# mbedTNC.net
KiCad netlist of a schematic drawn in EAGLE
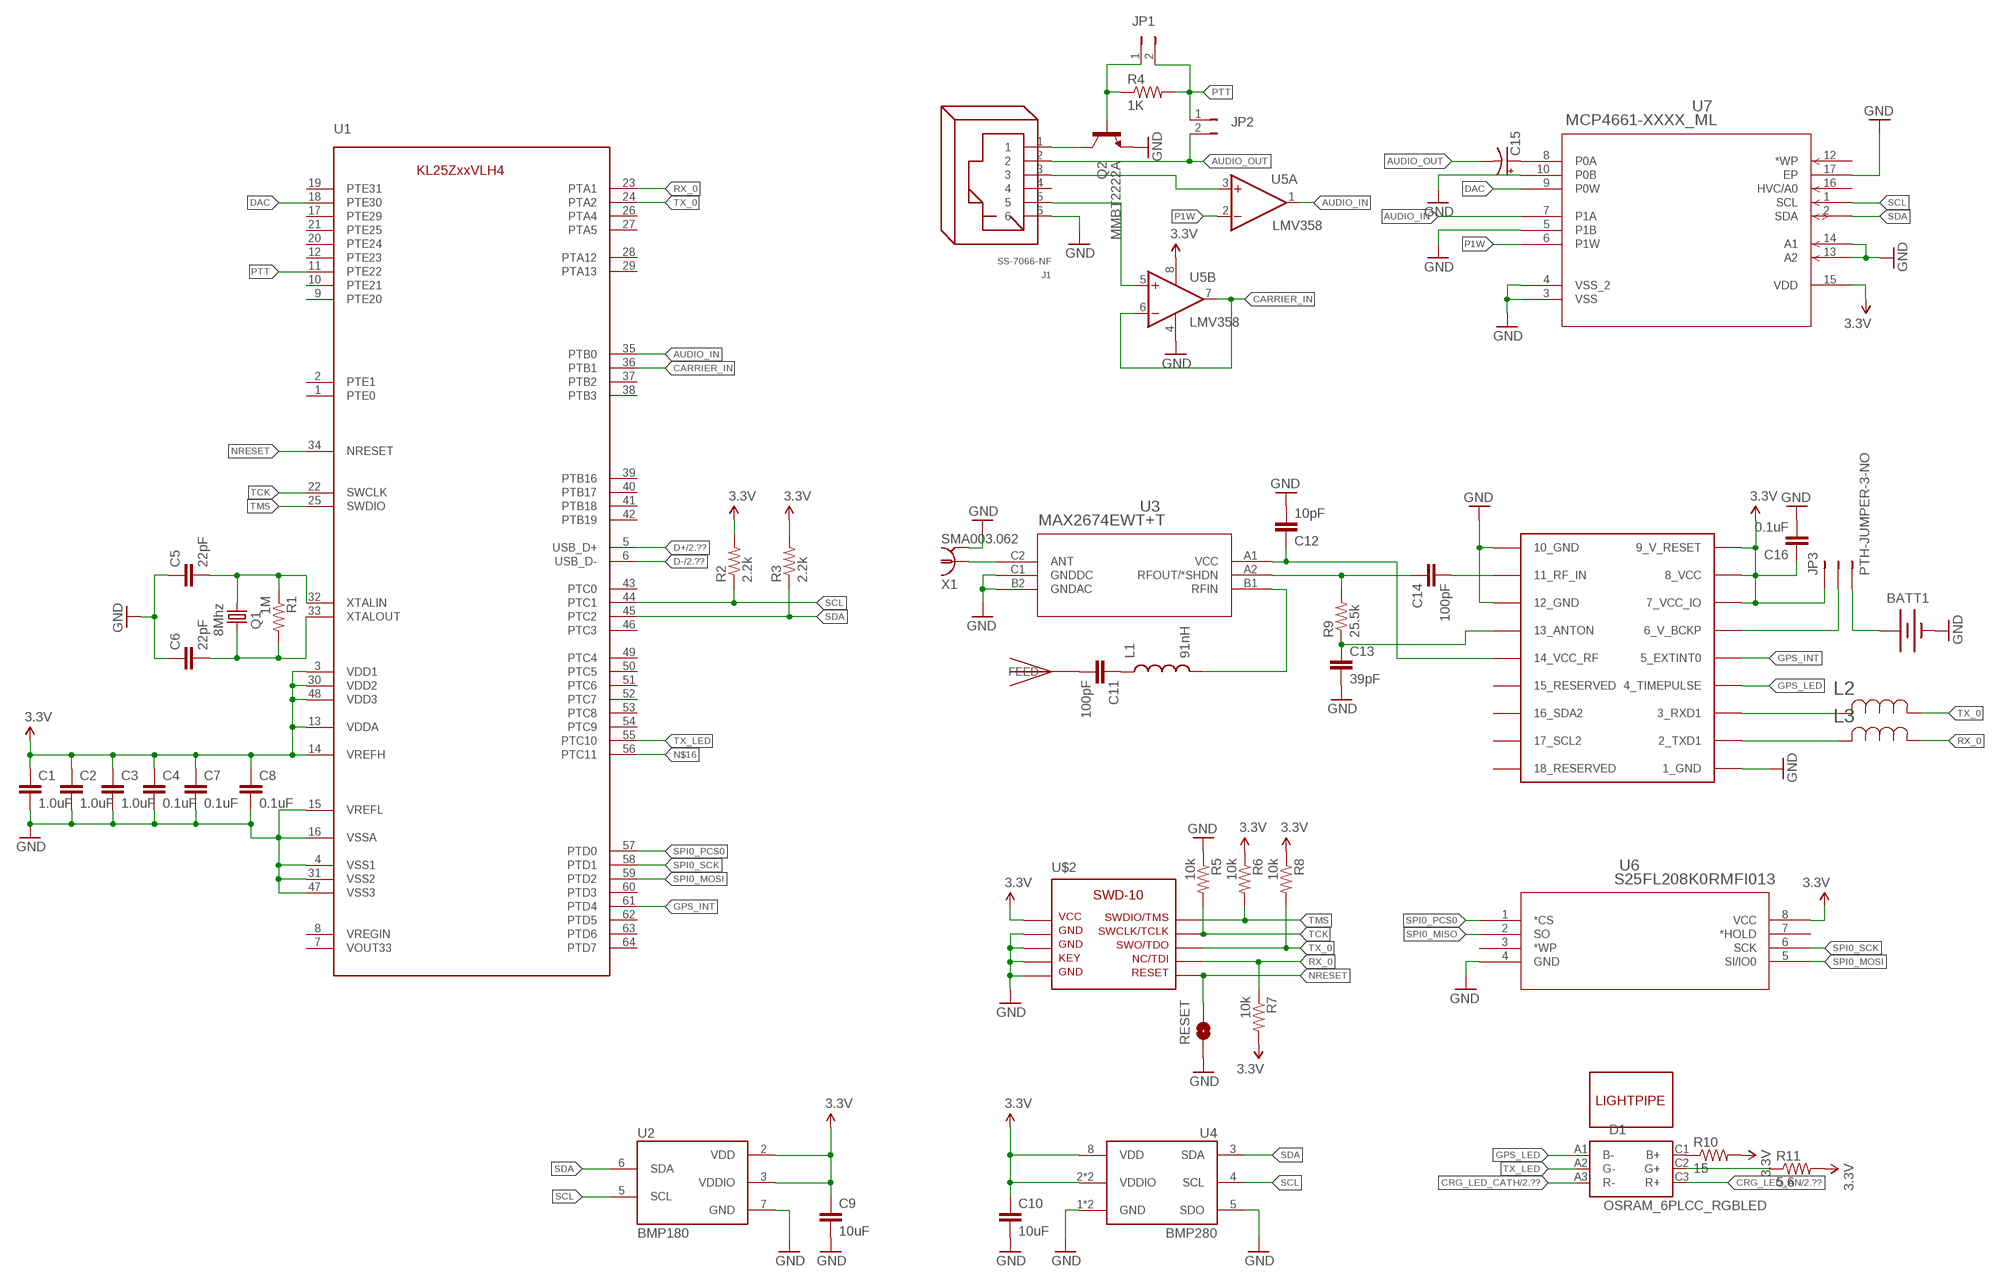
[diagram p0: schematic, sheet 1]
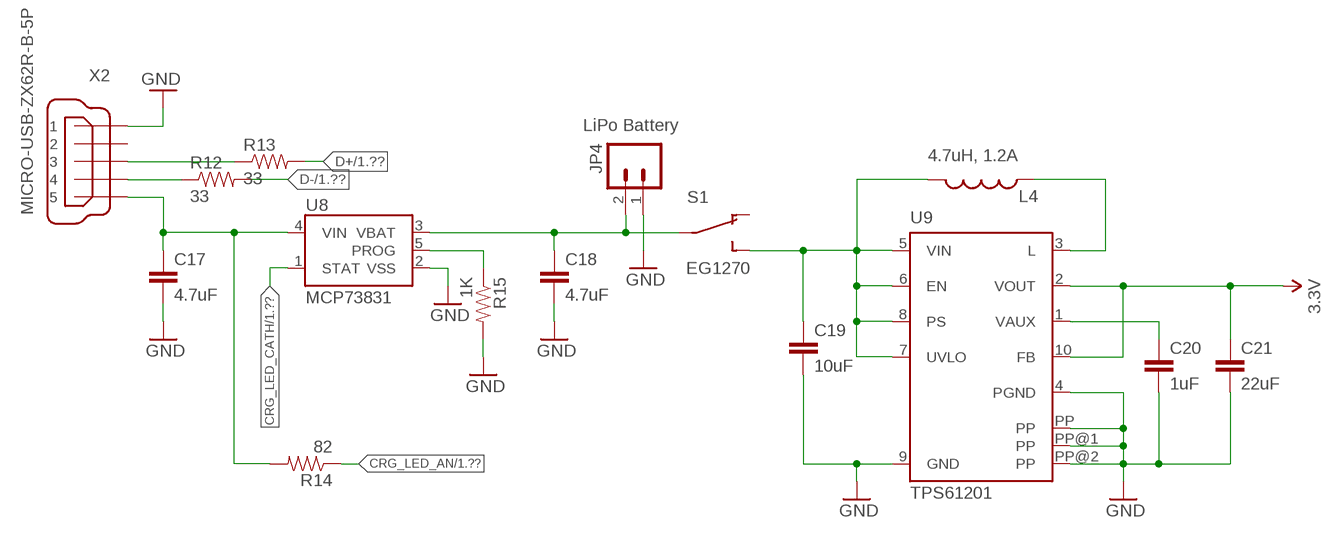
[diagram p1: schematic, sheet 2]

(export (version "E")
  (design (tool "Eeschema 10.0.6"))
  (components
    (comp (ref "C17")
      (value "4.7uF")
      (footprint "eagle-import:0805")
      (fields (field (name "MPN") "CL21B475KOFNNNE"))
      (libsource (lib "eagle-import") (part "SparkFun-Capacitors_CAP0805"))
    )
    (comp (ref "C18")
      (value "4.7uF")
      (footprint "eagle-import:0805")
      (fields (field (name "MPN") "CL21B475KOFNNNE"))
      (libsource (lib "eagle-import") (part "SparkFun-Capacitors_CAP0805"))
    )
    (comp (ref "C19")
      (value "10uF")
      (footprint "eagle-import:0805")
      (fields (field (name "MPN") "CL21A106KOQNNNE"))
      (libsource (lib "eagle-import") (part "SparkFun-Capacitors_CAP0805"))
    )
    (comp (ref "C20")
      (value "1uF")
      (footprint "eagle-import:0603-CAP")
      (fields (field (name "MPN") "EMK107B7105KA-T"))
      (libsource (lib "eagle-import") (part "SparkFun-Capacitors_CAP0603-CAP"))
    )
    (comp (ref "C21")
      (value "22uF")
      (footprint "eagle-import:1206")
      (fields (field (name "MPN") "CL31A226KOCLFNC"))
      (libsource (lib "eagle-import") (part "SparkFun-Capacitors_CAP1206"))
    )
    (comp (ref "JP4")
      (value "LiPo Battery")
      (footprint "eagle-import:JST-2-SMD")
      (fields (field (name "MPN") "S2B-PH-SM4-TB(LF)(SN)"))
      (libsource (lib "eagle-import") (part "M02-JST-2MM-SMT"))
    )
    (comp (ref "L4")
      (value "4.7uH, 1.2A")
      (footprint "eagle-import:CDRH2D09")
      (fields (field (name "MPN") "CDRH2D18/HPNP-4R7NC"))
      (libsource (lib "eagle-import") (part "INDUCTOR."))
    )
    (comp (ref "R12")
      (value "33")
      (footprint "eagle-import:0603-RES")
      (fields (field (name "MPN") "RMCF0603FT33R0"))
      (libsource (lib "eagle-import") (part "RESISTOR0603"))
    )
    (comp (ref "R13")
      (value "33")
      (footprint "eagle-import:0603-RES")
      (fields (field (name "MPN") "RMCF0603FT33R0"))
      (libsource (lib "eagle-import") (part "RESISTOR0603"))
    )
    (comp (ref "R14")
      (value "82")
      (footprint "eagle-import:0603-RES")
      (fields (field (name "MPN") "ESR03EZPJ820"))
      (libsource (lib "eagle-import") (part "RESISTOR0603"))
    )
    (comp (ref "R15")
      (value "1K")
      (footprint "eagle-import:0603-RES")
      (fields (field (name "MPN") "RMCF0603JT1K00"))
      (libsource (lib "eagle-import") (part "RESISTOR0603"))
    )
    (comp (ref "S1")
      (value "EG1270")
      (footprint "eagle-import:EG1270")
      (libsource (lib "eagle-import") (part "EG1270"))
    )
    (comp (ref "U8")
      (value "MCP73831")
      (footprint "eagle-import:SOT23-5")
      (libsource (lib "eagle-import") (part "MCP73831"))
    )
    (comp (ref "U9")
      (value "TPS61201")
      (footprint "eagle-import:S-PDSO-N10")
      (fields (field (name "MPN") "TPS61201DRCT"))
      (libsource (lib "eagle-import") (part "TPS61201"))
    )
    (comp (ref "X2")
      (value "MICRO-USB-ZX62R-B-5P")
      (footprint "eagle-import:ZX62R-B-5P")
      (fields (field (name "MPN") "ZX62R-B-5P"))
      (libsource (lib "eagle-import") (part "MICRO-USB-ZX62R-B-5P"))
    )
    (comp (ref "BATT1")
      (value "BK-890")
      (footprint "eagle-import:BATTCON_12MMPC")
      (libsource (lib "eagle-import") (part "BK-890"))
    )
    (comp (ref "C1")
      (value "1.0uF")
      (footprint "eagle-import:0603-CAP")
      (fields (field (name "MPN") "EMK107B7105KA-T"))
      (libsource (lib "eagle-import") (part "SparkFun-Capacitors_CAP0603-CAP"))
    )
    (comp (ref "C2")
      (value "1.0uF")
      (footprint "eagle-import:0603-CAP")
      (fields (field (name "MPN") "EMK107B7105KA-T"))
      (libsource (lib "eagle-import") (part "SparkFun-Capacitors_CAP0603-CAP"))
    )
    (comp (ref "C3")
      (value "1.0uF")
      (footprint "eagle-import:0603-CAP")
      (fields (field (name "MPN") "EMK107B7105KA-T"))
      (libsource (lib "eagle-import") (part "SparkFun-Capacitors_CAP0603-CAP"))
    )
    (comp (ref "C4")
      (value "0.1uF")
      (footprint "eagle-import:0603-CAP")
      (fields (field (name "MPN") "GRM188R71C104KA01D"))
      (libsource (lib "eagle-import") (part "SparkFun-Capacitors_CAP0603-CAP"))
    )
    (comp (ref "C5")
      (value "22pF")
      (footprint "eagle-import:0603-CAP")
      (fields (field (name "MPN") "C1608C0G1H220J080AA"))
      (libsource (lib "eagle-import") (part "SparkFun-Capacitors_CAP0603-CAP"))
    )
    (comp (ref "C6")
      (value "22pF")
      (footprint "eagle-import:0603-CAP")
      (fields (field (name "MPN") "C1608C0G1H220J080AA"))
      (libsource (lib "eagle-import") (part "SparkFun-Capacitors_CAP0603-CAP"))
    )
    (comp (ref "C7")
      (value "0.1uF")
      (footprint "eagle-import:0603-CAP")
      (fields (field (name "MPN") "GRM188R71C104KA01D"))
      (libsource (lib "eagle-import") (part "SparkFun-Capacitors_CAP0603-CAP"))
    )
    (comp (ref "C8")
      (value "0.1uF")
      (footprint "eagle-import:0603-CAP")
      (fields (field (name "MPN") "GRM188R71C104KA01D"))
      (libsource (lib "eagle-import") (part "SparkFun-Capacitors_CAP0603-CAP"))
    )
    (comp (ref "C9")
      (value "10uF")
      (footprint "eagle-import:0805")
      (fields (field (name "MPN") "CC0805KKX5R6BB106"))
      (libsource (lib "eagle-import") (part "SparkFun-Capacitors_CAP0805"))
    )
    (comp (ref "C10")
      (value "10uF")
      (footprint "eagle-import:0805")
      (fields (field (name "MPN") "CC0805KKX5R6BB106"))
      (libsource (lib "eagle-import") (part "SparkFun-Capacitors_CAP0805"))
    )
    (comp (ref "C11")
      (value "100pF")
      (footprint "eagle-import:0603-CAP")
      (fields (field (name "MPN") "CL10B101KB8NNNC"))
      (libsource (lib "eagle-import") (part "SparkFun-Capacitors_CAP0603-CAP"))
    )
    (comp (ref "C12")
      (value "10pF")
      (footprint "eagle-import:0603-CAP")
      (fields (field (name "MPN") "CL10C100CB8NNNC"))
      (libsource (lib "eagle-import") (part "SparkFun-Capacitors_CAP0603-CAP"))
    )
    (comp (ref "C13")
      (value "39pF")
      (footprint "eagle-import:0603-CAP")
      (fields (field (name "MPN") "CL10C390JB8NNNC"))
      (libsource (lib "eagle-import") (part "SparkFun-Capacitors_CAP0603-CAP"))
    )
    (comp (ref "C14")
      (value "100pF")
      (footprint "eagle-import:0603-CAP")
      (fields (field (name "MPN") "CL10B101KB8NNNC"))
      (libsource (lib "eagle-import") (part "SparkFun-Capacitors_CAP0603-CAP"))
    )
    (comp (ref "C15")
      (value "UWX1C100MCL2GB")
      (footprint "eagle-import:PCAP_4X5.4-ELECT")
      (libsource (lib "eagle-import") (part "UWX1C100MCL2GB"))
    )
    (comp (ref "C16")
      (value "0.1uF")
      (footprint "eagle-import:0603-CAP")
      (fields (field (name "MPN") "GRM188R71C104KA01D"))
      (libsource (lib "eagle-import") (part "CAP0603-CAP"))
    )
    (comp (ref "D1")
      (value "OSRAM_6PLCC_RGBLED")
      (footprint "eagle-import:LRTB-GFTM")
      (fields (field (name "MPN") "LRTBGFTM-ST7-1+VV9-29+Q5R"))
      (libsource (lib "eagle-import") (part "OSRAM_6PLCC_RGBLED"))
    )
    (comp (ref "J1")
      (value "SS-7066-NF")
      (footprint "eagle-import:SS-7066-NF")
      (libsource (lib "eagle-import") (part "SS-7066-NF"))
    )
    (comp (ref "JP1")
      (value "JUMPER-PTH-2-NO")
      (footprint "eagle-import:PTH-JUMPER-2-NO_NO_SILK")
      (libsource (lib "eagle-import") (part "JUMPER-PTH-2-NO"))
    )
    (comp (ref "JP2")
      (value "JUMPER-PTH-2-NO")
      (footprint "eagle-import:PTH-JUMPER-2-NO_NO_SILK")
      (libsource (lib "eagle-import") (part "JUMPER-PTH-2-NO"))
    )
    (comp (ref "JP3")
      (value "PTH-JUMPER-3-NO")
      (footprint "eagle-import:PTH-JUMPER-3-NO")
      (libsource (lib "eagle-import") (part "PTH-JUMPER-3-NO"))
    )
    (comp (ref "L1")
      (value "91nH")
      (footprint "eagle-import:0603")
      (fields (field (name "MPN") "LQW18AN91NJ00D"))
      (libsource (lib "eagle-import") (part "INDUCTOR0603"))
    )
    (comp (ref "L2")
      (value "BLM18HG102SN1D")
      (footprint "eagle-import:IND_BLM18_0603")
      (libsource (lib "eagle-import") (part "BLM18HG102SN1D"))
    )
    (comp (ref "L3")
      (value "BLM18HG102SN1D")
      (footprint "eagle-import:IND_BLM18_0603")
      (libsource (lib "eagle-import") (part "BLM18HG102SN1D"))
    )
    (comp (ref "Q1")
      (value "8Mhz")
      (footprint "eagle-import:CRYSTAL_5X3.2")
      (fields (field (name "MPN") "7A-8.000MAAJ-T "))
      (libsource (lib "eagle-import") (part "CRYSTALCRYSTAL_5X3.2"))
    )
    (comp (ref "Q2")
      (value "MMBT2222A")
      (footprint "eagle-import:SOT23-3")
      (fields (field (name "MPN") "MMBT2222ALT3G"))
      (libsource (lib "eagle-import") (part "TRANSISTOR_NPNMMBT2222A"))
    )
    (comp (ref "R1")
      (value "1M")
      (footprint "eagle-import:0603-RES")
      (fields (field (name "MPN") "RMCF0603FT1M00"))
      (libsource (lib "eagle-import") (part "RESISTOR0603"))
    )
    (comp (ref "R2")
      (value "2.2k")
      (footprint "eagle-import:0603-RES")
      (fields (field (name "MPN") "RMCF0603JT2K20"))
      (libsource (lib "eagle-import") (part "RESISTOR0603-RES"))
    )
    (comp (ref "R3")
      (value "2.2k")
      (footprint "eagle-import:0603-RES")
      (fields (field (name "MPN") "RMCF0603JT2K20"))
      (libsource (lib "eagle-import") (part "RESISTOR0603-RES"))
    )
    (comp (ref "R4")
      (value "1K")
      (footprint "eagle-import:0603-RES")
      (fields (field (name "MPN") "RMCF0603JT1K00"))
      (libsource (lib "eagle-import") (part "RESISTOR0603"))
    )
    (comp (ref "R5")
      (value "10k")
      (footprint "eagle-import:0603-RES")
      (fields (field (name "MPN") "RNCP0603FTD10K0"))
      (libsource (lib "eagle-import") (part "RESISTOR0603"))
    )
    (comp (ref "R6")
      (value "10k")
      (footprint "eagle-import:0603-RES")
      (fields (field (name "MPN") "RNCP0603FTD10K0"))
      (libsource (lib "eagle-import") (part "RESISTOR0603"))
    )
    (comp (ref "R7")
      (value "10k")
      (footprint "eagle-import:0603-RES")
      (fields (field (name "MPN") "RNCP0603FTD10K0"))
      (libsource (lib "eagle-import") (part "RESISTOR0603"))
    )
    (comp (ref "R8")
      (value "10k")
      (footprint "eagle-import:0603-RES")
      (fields (field (name "MPN") "RNCP0603FTD10K0"))
      (libsource (lib "eagle-import") (part "RESISTOR0603"))
    )
    (comp (ref "R9")
      (value "25.5k")
      (footprint "eagle-import:0603-RES")
      (fields (field (name "MPN") "RMCF0603FT25K5"))
      (libsource (lib "eagle-import") (part "RESISTOR0603"))
    )
    (comp (ref "R10")
      (value "15")
      (footprint "eagle-import:0603-RES")
      (fields (field (name "MPN") "RMCF0603JT15R0"))
      (libsource (lib "eagle-import") (part "RESISTOR0603"))
    )
    (comp (ref "R11")
      (value "5.6")
      (footprint "eagle-import:0603-RES")
      (fields (field (name "MPN") "RMCF0603FT5R60"))
      (libsource (lib "eagle-import") (part "RESISTOR0603"))
    )
    (comp (ref "RESET")
      (value "JUMPER-PAD-2-NOYES_SILK")
      (footprint "eagle-import:PAD-JUMPER-2-NO_YES_SILK")
      (libsource (lib "eagle-import") (part "JUMPER-PAD-2-NOYES_SILK"))
    )
    (comp (ref "U$1")
      (value "JTI_ANTENNA-1575AT43A40")
      (footprint "eagle-import:JTI_ANTENNA-1575AT43A40")
      (fields (field (name "MPN") "1575AT43A0040E"))
      (libsource (lib "eagle-import") (part "JTI_ANTENNA-1575AT43A40"))
    )
    (comp (ref "U$2")
      (value "SWD-10")
      (footprint "eagle-import:M50-3600542")
      (libsource (lib "eagle-import") (part "SWD-10"))
    )
    (comp (ref "U$3")
      (value "UBLOX_MAX")
      (footprint "eagle-import:UBLOX_MAX")
      (fields (field (name "MPN") "MAX-7Q"))
      (libsource (lib "eagle-import") (part "UBLOX_MAX"))
    )
    (comp (ref "U$4")
      (value "VLP-ZZZ-X")
      (footprint "eagle-import:VLP-ZZZ-X")
      (fields (field (name "MPN") "VLP-500-F"))
      (libsource (lib "eagle-import") (part "VLP-ZZZ-X"))
    )
    (comp (ref "U1")
      (value "MKL25ZXXVLH4")
      (footprint "eagle-import:64-LQFP")
      (libsource (lib "eagle-import") (part "MKL25ZXXVLH4"))
    )
    (comp (ref "U2")
      (value "BMP180")
      (footprint "eagle-import:BMP180")
      (libsource (lib "eagle-import") (part "BMP180"))
    )
    (comp (ref "U3")
      (value "MAX2674EWT+T")
      (footprint "eagle-import:21-0217D_W61B1-1")
      (libsource (lib "eagle-import") (part "MAX2674EWT+T"))
    )
    (comp (ref "U4")
      (value "BMP280")
      (footprint "eagle-import:BMP280")
      (libsource (lib "eagle-import") (part "BMP280"))
    )
    (comp (ref "U5")
      (value "LMV358")
      (footprint "eagle-import:DDU8-M")
      (fields (field (name "MPN") "LMV358IDDUR"))
      (libsource (lib "eagle-import") (part "LMV358"))
    )
    (comp (ref "U6")
      (value "S25FL208K0RMFI013")
      (footprint "eagle-import:SO-8_SOA008")
      (libsource (lib "eagle-import") (part "S25FL208K0RMFI013"))
    )
    (comp (ref "U7")
      (value "MCP4661-XXXX_ML")
      (footprint "eagle-import:QFN16_4X4MC")
      (fields (field (name "MPN") "MCP4661T-103E/ML"))
      (libsource (lib "eagle-import") (part "MCP4661-XXXX_ML"))
    )
    (comp (ref "X1")
      (value "SMA003.062")
      (footprint "eagle-import:SMA003.062")
      (fields (field (name "MPN") "consma003.062"))
      (libsource (lib "eagle-import") (part "SMA003.062"))
    )
  )
  (nets
    (net (code "1") (name "3.3V") (class "Default")
      (node (ref "C1") (pin "1") (pinfunction "1_1") (pintype "passive"))
      (node (ref "C10") (pin "1") (pinfunction "1_1") (pintype "passive"))
      (node (ref "C16") (pin "1") (pinfunction "1_1") (pintype "passive"))
      (node (ref "C2") (pin "1") (pinfunction "1_1") (pintype "passive"))
      (node (ref "C21") (pin "1") (pinfunction "1_1") (pintype "passive"))
      (node (ref "C3") (pin "1") (pinfunction "1_1") (pintype "passive"))
      (node (ref "C4") (pin "1") (pinfunction "1_1") (pintype "passive"))
      (node (ref "C7") (pin "1") (pinfunction "1_1") (pintype "passive"))
      (node (ref "C8") (pin "1") (pinfunction "1_1") (pintype "passive"))
      (node (ref "C9") (pin "1") (pinfunction "1_1") (pintype "passive"))
      (node (ref "JP3") (pin "1") (pinfunction "1_1") (pintype "passive"))
      (node (ref "R10") (pin "2") (pinfunction "2_2") (pintype "passive"))
      (node (ref "R11") (pin "2") (pinfunction "2_2") (pintype "passive"))
      (node (ref "R2") (pin "2") (pinfunction "2_2") (pintype "passive"))
      (node (ref "R3") (pin "2") (pinfunction "2_2") (pintype "passive"))
      (node (ref "R6") (pin "1") (pinfunction "1_1") (pintype "passive"))
      (node (ref "R7") (pin "2") (pinfunction "2_2") (pintype "passive"))
      (node (ref "R8") (pin "1") (pinfunction "1_1") (pintype "passive"))
      (node (ref "U$2") (pin "P$1") (pinfunction "1_P$1") (pintype "bidirectional"))
      (node (ref "U$3") (pin "7_VCC_IO") (pinfunction "7_VCC_IO_7_VCC_IO") (pintype "power_in"))
      (node (ref "U$3") (pin "8_VCC") (pinfunction "8_VCC_8_VCC") (pintype "power_in"))
      (node (ref "U$3") (pin "9_V_RESET") (pinfunction "9_V_RESET_9_V_RESET") (pintype "power_in"))
      (node (ref "U1") (pin "13") (pinfunction "VDDA_13") (pintype "bidirectional"))
      (node (ref "U1") (pin "14") (pinfunction "VREFH_14") (pintype "bidirectional"))
      (node (ref "U1") (pin "3") (pinfunction "VDD1_3") (pintype "bidirectional"))
      (node (ref "U1") (pin "30") (pinfunction "VDD2_30") (pintype "bidirectional"))
      (node (ref "U1") (pin "48") (pinfunction "VDD3_48") (pintype "bidirectional"))
      (node (ref "U2") (pin "2") (pinfunction "VDD_2") (pintype "power_in"))
      (node (ref "U2") (pin "3") (pinfunction "VDDIO_3") (pintype "power_in"))
      (node (ref "U4") (pin "2") (pinfunction "VDDIO_2") (pintype "power_in"))
      (node (ref "U4") (pin "6") (pinfunction "VDDIO_6") (pintype "power_in"))
      (node (ref "U4") (pin "8") (pinfunction "VDD_8") (pintype "power_in"))
      (node (ref "U5") (pin "8") (pinfunction "V+_8") (pintype "power_in"))
      (node (ref "U6") (pin "8") (pinfunction "VCC_8") (pintype "power_in"))
      (node (ref "U7") (pin "15") (pinfunction "VDD_15") (pintype "power_in"))
      (node (ref "U9") (pin "10") (pinfunction "FB_10") (pintype "input"))
      (node (ref "U9") (pin "2") (pinfunction "VOUT_2") (pintype "passive"))
    )
    (net (code "2") (name "AUDIO_IN") (class "Default")
      (node (ref "U1") (pin "35") (pinfunction "PTB0_35") (pintype "bidirectional"))
      (node (ref "U5") (pin "1") (pinfunction "OUT_1") (pintype "output"))
      (node (ref "U7") (pin "7") (pinfunction "P1A_7") (pintype "passive"))
    )
    (net (code "3") (name "AUDIO_OUT") (class "Default")
      (node (ref "C15") (pin "2") (pinfunction "-_2") (pintype "passive"))
      (node (ref "J1") (pin "2") (pinfunction "2_2") (pintype "bidirectional"))
      (node (ref "JP2") (pin "2") (pinfunction "2_2") (pintype "passive"))
    )
    (net (code "4") (name "CARRIER_IN") (class "Default")
      (node (ref "U1") (pin "36") (pinfunction "PTB1_36") (pintype "bidirectional"))
      (node (ref "U5") (pin "6") (pinfunction "-IN_6") (pintype "input"))
      (node (ref "U5") (pin "7") (pinfunction "OUT_7") (pintype "output"))
    )
    (net (code "5") (name "CRG_LED_AN") (class "Default")
      (node (ref "D1") (pin "C3") (pinfunction "R+_C3") (pintype "power_in"))
      (node (ref "R14") (pin "1") (pinfunction "1_1") (pintype "passive"))
    )
    (net (code "6") (name "CRG_LED_CATH") (class "Default")
      (node (ref "D1") (pin "A3") (pinfunction "R-_A3") (pintype "power_in"))
      (node (ref "U8") (pin "1") (pinfunction "STAT_1") (pintype "output"))
    )
    (net (code "7") (name "D+") (class "Default")
      (node (ref "R13") (pin "2") (pinfunction "2_2") (pintype "passive"))
      (node (ref "U1") (pin "5") (pinfunction "USB_D+_5") (pintype "bidirectional"))
    )
    (net (code "8") (name "D-") (class "Default")
      (node (ref "R12") (pin "2") (pinfunction "2_2") (pintype "passive"))
      (node (ref "U1") (pin "6") (pinfunction "USB_D-_6") (pintype "bidirectional"))
    )
    (net (code "9") (name "DAC") (class "Default")
      (node (ref "U1") (pin "18") (pinfunction "PTE30_18") (pintype "bidirectional"))
      (node (ref "U7") (pin "9") (pinfunction "P0W_9") (pintype "passive"))
    )
    (net (code "10") (name "GND") (class "Default")
      (node (ref "BATT1") (pin "C1") (pinfunction "-_C1") (pintype "power_in"))
      (node (ref "C1") (pin "2") (pinfunction "2_2") (pintype "passive"))
      (node (ref "C10") (pin "2") (pinfunction "2_2") (pintype "passive"))
      (node (ref "C12") (pin "2") (pinfunction "2_2") (pintype "passive"))
      (node (ref "C13") (pin "2") (pinfunction "2_2") (pintype "passive"))
      (node (ref "C16") (pin "2") (pinfunction "2_2") (pintype "passive"))
      (node (ref "C17") (pin "2") (pinfunction "2_2") (pintype "passive"))
      (node (ref "C18") (pin "2") (pinfunction "2_2") (pintype "passive"))
      (node (ref "C19") (pin "2") (pinfunction "2_2") (pintype "passive"))
      (node (ref "C2") (pin "2") (pinfunction "2_2") (pintype "passive"))
      (node (ref "C20") (pin "2") (pinfunction "2_2") (pintype "passive"))
      (node (ref "C21") (pin "2") (pinfunction "2_2") (pintype "passive"))
      (node (ref "C3") (pin "2") (pinfunction "2_2") (pintype "passive"))
      (node (ref "C4") (pin "2") (pinfunction "2_2") (pintype "passive"))
      (node (ref "C5") (pin "1") (pinfunction "1_1") (pintype "passive"))
      (node (ref "C6") (pin "1") (pinfunction "1_1") (pintype "passive"))
      (node (ref "C7") (pin "2") (pinfunction "2_2") (pintype "passive"))
      (node (ref "C8") (pin "2") (pinfunction "2_2") (pintype "passive"))
      (node (ref "C9") (pin "2") (pinfunction "2_2") (pintype "passive"))
      (node (ref "J1") (pin "6") (pinfunction "6_6") (pintype "bidirectional"))
      (node (ref "JP4") (pin "1") (pinfunction "1_1") (pintype "passive"))
      (node (ref "Q2") (pin "2") (pinfunction "E_2") (pintype "passive"))
      (node (ref "R15") (pin "2") (pinfunction "2_2") (pintype "passive"))
      (node (ref "R5") (pin "1") (pinfunction "1_1") (pintype "passive"))
      (node (ref "RESET") (pin "1") (pinfunction "1_1") (pintype "passive"))
      (node (ref "U$2") (pin "P$3") (pinfunction "3_P$3") (pintype "bidirectional"))
      (node (ref "U$2") (pin "P$5") (pinfunction "5_P$5") (pintype "bidirectional"))
      (node (ref "U$2") (pin "P$7") (pinfunction "7_P$7") (pintype "bidirectional"))
      (node (ref "U$2") (pin "P$9") (pinfunction "9_P$9") (pintype "bidirectional"))
      (node (ref "U$3") (pin "10_GND") (pinfunction "10_GND_10_GND") (pintype "power_in"))
      (node (ref "U$3") (pin "12_GND") (pinfunction "12_GND_12_GND") (pintype "power_in"))
      (node (ref "U$3") (pin "1_GND") (pinfunction "1_GND_1_GND") (pintype "power_in"))
      (node (ref "U1") (pin "15") (pinfunction "VREFL_15") (pintype "bidirectional"))
      (node (ref "U1") (pin "16") (pinfunction "VSSA_16") (pintype "bidirectional"))
      (node (ref "U1") (pin "31") (pinfunction "VSS2_31") (pintype "bidirectional"))
      (node (ref "U1") (pin "4") (pinfunction "VSS1_4") (pintype "bidirectional"))
      (node (ref "U1") (pin "47") (pinfunction "VSS3_47") (pintype "bidirectional"))
      (node (ref "U2") (pin "7") (pinfunction "GND_7") (pintype "power_in"))
      (node (ref "U3") (pin "B2") (pinfunction "GNDAC_B2") (pintype "power_in"))
      (node (ref "U3") (pin "C1") (pinfunction "GNDDC_C1") (pintype "power_in"))
      (node (ref "U4") (pin "1") (pinfunction "GND_1") (pintype "power_in"))
      (node (ref "U4") (pin "5") (pinfunction "SDO_5") (pintype "bidirectional"))
      (node (ref "U4") (pin "7") (pinfunction "GND_7") (pintype "power_in"))
      (node (ref "U5") (pin "4") (pinfunction "V-_4") (pintype "power_in"))
      (node (ref "U6") (pin "4") (pinfunction "GND_4") (pintype "power_in"))
      (node (ref "U7") (pin "10") (pinfunction "P0B_10") (pintype "passive"))
      (node (ref "U7") (pin "13") (pinfunction "A2_13") (pintype "input"))
      (node (ref "U7") (pin "14") (pinfunction "A1_14") (pintype "input"))
      (node (ref "U7") (pin "17") (pinfunction "EP_17") (pintype "passive"))
      (node (ref "U7") (pin "3") (pinfunction "VSS_3") (pintype "power_in"))
      (node (ref "U7") (pin "4") (pinfunction "VSS_2_4") (pintype "power_in"))
      (node (ref "U7") (pin "5") (pinfunction "P1B_5") (pintype "passive"))
      (node (ref "U8") (pin "2") (pinfunction "VSS_2") (pintype "power_in"))
      (node (ref "U9") (pin "4") (pinfunction "PGND_4") (pintype "power_in"))
      (node (ref "U9") (pin "9") (pinfunction "GND_9") (pintype "power_in"))
      (node (ref "U9") (pin "PP") (pinfunction "PP_PP") (pintype "power_in"))
      (node (ref "U9") (pin "PP@1") (pinfunction "PP_PP@1") (pintype "power_in"))
      (node (ref "U9") (pin "PP@2") (pinfunction "PP_PP@2") (pintype "power_in"))
      (node (ref "X1") (pin "C2") (pinfunction "2_C2") (pintype "passive"))
      (node (ref "X1") (pin "C3") (pinfunction "2_C3") (pintype "passive"))
      (node (ref "X1") (pin "C4") (pinfunction "2_C4") (pintype "passive"))
      (node (ref "X1") (pin "C5") (pinfunction "2_C5") (pintype "passive"))
      (node (ref "X2") (pin "1") (pinfunction "1_1") (pintype "input"))
    )
    (net (code "11") (name "GPS_INT") (class "Default")
      (node (ref "U$3") (pin "5_EXTINT0") (pinfunction "5_EXTINT0_5_EXTINT0") (pintype "bidirectional"))
      (node (ref "U1") (pin "61") (pinfunction "PTD4_61") (pintype "bidirectional"))
    )
    (net (code "12") (name "GPS_LED") (class "Default")
      (node (ref "D1") (pin "A1") (pinfunction "B-_A1") (pintype "power_in"))
      (node (ref "U$3") (pin "4_TIMEPULSE") (pinfunction "4_TIMEPULSE_4_TIMEPULSE") (pintype "bidirectional"))
    )
    (net (code "13") (name "N$16") (class "Default")
      (node (ref "U1") (pin "56") (pinfunction "PTC11_56") (pintype "bidirectional"))
    )
    (net (code "14") (name "NRESET") (class "Default")
      (node (ref "RESET") (pin "2") (pinfunction "2_2") (pintype "passive"))
      (node (ref "U$2") (pin "P$10") (pinfunction "10_P$10") (pintype "bidirectional"))
      (node (ref "U1") (pin "34") (pinfunction "NRESET_34") (pintype "bidirectional"))
    )
    (net (code "15") (name "Net-(BATT1-+-PadC2)") (class "Default")
      (node (ref "BATT1") (pin "C2") (pinfunction "+_C2") (pintype "power_in"))
      (node (ref "BATT1") (pin "C3") (pinfunction "+_C3") (pintype "power_in"))
      (node (ref "JP3") (pin "3") (pinfunction "3_3") (pintype "passive"))
    )
    (net (code "16") (name "Net-(C11-Pad1)") (class "Default")
      (node (ref "C11") (pin "1") (pinfunction "1_1") (pintype "passive"))
      (node (ref "L1") (pin "1") (pinfunction "1_1") (pintype "passive"))
    )
    (net (code "17") (name "Net-(C11-Pad2)") (class "Default")
      (node (ref "C11") (pin "2") (pinfunction "2_2") (pintype "passive"))
      (node (ref "U$1") (pin "FEED") (pinfunction "FEED_FEED") (pintype "bidirectional"))
    )
    (net (code "18") (name "Net-(C13-Pad1)") (class "Default")
      (node (ref "C13") (pin "1") (pinfunction "1_1") (pintype "passive"))
      (node (ref "R9") (pin "1") (pinfunction "1_1") (pintype "passive"))
      (node (ref "U$3") (pin "13_ANTON") (pinfunction "13_ANTON_13_ANTON") (pintype "bidirectional"))
    )
    (net (code "19") (name "Net-(C14-Pad2)") (class "Default")
      (node (ref "C14") (pin "2") (pinfunction "2_2") (pintype "passive"))
      (node (ref "U$3") (pin "11_RF_IN") (pinfunction "11_RF_IN_11_RF_IN") (pintype "bidirectional"))
    )
    (net (code "20") (name "Net-(C15-+)") (class "Default")
      (node (ref "C15") (pin "1") (pinfunction "+_1") (pintype "passive"))
      (node (ref "U7") (pin "8") (pinfunction "P0A_8") (pintype "passive"))
    )
    (net (code "21") (name "Net-(D1-B+)") (class "Default")
      (node (ref "D1") (pin "C1") (pinfunction "B+_C1") (pintype "power_in"))
      (node (ref "R10") (pin "1") (pinfunction "1_1") (pintype "passive"))
    )
    (net (code "22") (name "Net-(D1-G+)") (class "Default")
      (node (ref "D1") (pin "C2") (pinfunction "G+_C2") (pintype "power_in"))
      (node (ref "R11") (pin "1") (pinfunction "1_1") (pintype "passive"))
    )
    (net (code "23") (name "Net-(JP3-Pad2)") (class "Default")
      (node (ref "JP3") (pin "2") (pinfunction "2_2") (pintype "passive"))
      (node (ref "U$3") (pin "6_V_BCKP") (pinfunction "6_V_BCKP_6_V_BCKP") (pintype "bidirectional"))
    )
    (net (code "24") (name "Net-(L2-Pad2)") (class "Default")
      (node (ref "L2") (pin "2") (pinfunction "2_2") (pintype "passive"))
      (node (ref "U$3") (pin "3_RXD1") (pinfunction "3_RXD1_3_RXD1") (pintype "bidirectional"))
    )
    (net (code "25") (name "Net-(L3-Pad2)") (class "Default")
      (node (ref "L3") (pin "2") (pinfunction "2_2") (pintype "passive"))
      (node (ref "U$3") (pin "2_TXD1") (pinfunction "2_TXD1_2_TXD1") (pintype "bidirectional"))
    )
    (net (code "26") (name "Net-(L4-1)") (class "Default")
      (node (ref "L4") (pin "P$1") (pinfunction "1_P$1") (pintype "passive"))
      (node (ref "U9") (pin "3") (pinfunction "L_3") (pintype "input"))
    )
    (net (code "27") (name "Net-(L4-2)") (class "Default")
      (node (ref "C19") (pin "1") (pinfunction "1_1") (pintype "passive"))
      (node (ref "L4") (pin "P$2") (pinfunction "2_P$2") (pintype "passive"))
      (node (ref "S1") (pin "P$3") (pinfunction "O2_P$3") (pintype "passive"))
      (node (ref "U9") (pin "5") (pinfunction "VIN_5") (pintype "input"))
      (node (ref "U9") (pin "6") (pinfunction "EN_6") (pintype "input"))
      (node (ref "U9") (pin "7") (pinfunction "UVLO_7") (pintype "input"))
      (node (ref "U9") (pin "8") (pinfunction "PS_8") (pintype "input"))
    )
    (net (code "28") (name "Net-(Q1-1)") (class "Default")
      (node (ref "C6") (pin "2") (pinfunction "2_2") (pintype "passive"))
      (node (ref "Q1") (pin "P$1") (pinfunction "1_P$1") (pintype "passive"))
      (node (ref "R1") (pin "2") (pinfunction "2_2") (pintype "passive"))
      (node (ref "U1") (pin "33") (pinfunction "XTALOUT_33") (pintype "bidirectional"))
    )
    (net (code "29") (name "Net-(Q1-2)") (class "Default")
      (node (ref "C5") (pin "2") (pinfunction "2_2") (pintype "passive"))
      (node (ref "Q1") (pin "P$2") (pinfunction "2_P$2") (pintype "passive"))
      (node (ref "R1") (pin "1") (pinfunction "1_1") (pintype "passive"))
      (node (ref "U1") (pin "32") (pinfunction "XTALIN_32") (pintype "bidirectional"))
    )
    (net (code "30") (name "Net-(Q2-B)") (class "Default")
      (node (ref "JP1") (pin "1") (pinfunction "1_1") (pintype "passive"))
      (node (ref "Q2") (pin "1") (pinfunction "B_1") (pintype "passive"))
      (node (ref "R4") (pin "1") (pinfunction "1_1") (pintype "passive"))
    )
    (net (code "31") (name "Net-(Q2-C)") (class "Default")
      (node (ref "J1") (pin "1") (pinfunction "1_1") (pintype "bidirectional"))
      (node (ref "Q2") (pin "3") (pinfunction "C_3") (pintype "passive"))
    )
    (net (code "32") (name "Net-(R12-Pad1)") (class "Default")
      (node (ref "R12") (pin "1") (pinfunction "1_1") (pintype "passive"))
      (node (ref "X2") (pin "4") (pinfunction "4_4") (pintype "input"))
    )
    (net (code "33") (name "Net-(R13-Pad1)") (class "Default")
      (node (ref "R13") (pin "1") (pinfunction "1_1") (pintype "passive"))
      (node (ref "X2") (pin "3") (pinfunction "3_3") (pintype "input"))
    )
    (net (code "34") (name "Net-(S1-P)") (class "Default")
      (node (ref "C18") (pin "1") (pinfunction "1_1") (pintype "passive"))
      (node (ref "JP4") (pin "2") (pinfunction "2_2") (pintype "passive"))
      (node (ref "S1") (pin "P$2") (pinfunction "P_P$2") (pintype "passive"))
      (node (ref "U8") (pin "3") (pinfunction "VBAT_3") (pintype "power_in"))
    )
    (net (code "35") (name "Net-(U3-ANT)") (class "Default")
      (node (ref "U3") (pin "C2") (pinfunction "ANT_C2") (pintype "passive"))
      (node (ref "X1") (pin "RF") (pinfunction "1_RF") (pintype "passive"))
    )
    (net (code "36") (name "Net-(U3-RFIN)") (class "Default")
      (node (ref "L1") (pin "2") (pinfunction "2_2") (pintype "passive"))
      (node (ref "U3") (pin "B1") (pinfunction "RFIN_B1") (pintype "input"))
    )
    (net (code "37") (name "Net-(U3-RFOUT{slash}*SHDN)") (class "Default")
      (node (ref "C14") (pin "1") (pinfunction "1_1") (pintype "passive"))
      (node (ref "R9") (pin "2") (pinfunction "2_2") (pintype "passive"))
      (node (ref "U3") (pin "A2") (pinfunction "RFOUT/*SHDN_A2") (pintype "passive"))
    )
    (net (code "38") (name "Net-(U3-VCC)") (class "Default")
      (node (ref "C12") (pin "1") (pinfunction "1_1") (pintype "passive"))
      (node (ref "U$3") (pin "14_VCC_RF") (pinfunction "14_VCC_RF_14_VCC_RF") (pintype "bidirectional"))
      (node (ref "U3") (pin "A1") (pinfunction "VCC_A1") (pintype "power_in"))
    )
    (net (code "39") (name "Net-(U5A-+IN)") (class "Default")
      (node (ref "J1") (pin "3") (pinfunction "3_3") (pintype "bidirectional"))
      (node (ref "U5") (pin "3") (pinfunction "+IN_3") (pintype "input"))
    )
    (net (code "40") (name "Net-(U5B-+IN)") (class "Default")
      (node (ref "J1") (pin "5") (pinfunction "5_5") (pintype "bidirectional"))
      (node (ref "U5") (pin "5") (pinfunction "+IN_5") (pintype "input"))
    )
    (net (code "41") (name "Net-(U8-PROG)") (class "Default")
      (node (ref "R15") (pin "1") (pinfunction "1_1") (pintype "passive"))
      (node (ref "U8") (pin "5") (pinfunction "PROG_5") (pintype "input"))
    )
    (net (code "42") (name "Net-(U8-VIN)") (class "Default")
      (node (ref "C17") (pin "1") (pinfunction "1_1") (pintype "passive"))
      (node (ref "R14") (pin "2") (pinfunction "2_2") (pintype "passive"))
      (node (ref "U8") (pin "4") (pinfunction "VIN_4") (pintype "power_in"))
      (node (ref "X2") (pin "5") (pinfunction "5_5") (pintype "input"))
    )
    (net (code "43") (name "Net-(U9-VAUX)") (class "Default")
      (node (ref "C20") (pin "1") (pinfunction "1_1") (pintype "passive"))
      (node (ref "U9") (pin "1") (pinfunction "VAUX_1") (pintype "bidirectional"))
    )
    (net (code "44") (name "P1W") (class "Default")
      (node (ref "U5") (pin "2") (pinfunction "-IN_2") (pintype "input"))
      (node (ref "U7") (pin "6") (pinfunction "P1W_6") (pintype "passive"))
    )
    (net (code "45") (name "PTT") (class "Default")
      (node (ref "JP1") (pin "2") (pinfunction "2_2") (pintype "passive"))
      (node (ref "JP2") (pin "1") (pinfunction "1_1") (pintype "passive"))
      (node (ref "R4") (pin "2") (pinfunction "2_2") (pintype "passive"))
      (node (ref "U1") (pin "11") (pinfunction "PTE22_11") (pintype "bidirectional"))
    )
    (net (code "46") (name "RX_0") (class "Default")
      (node (ref "L3") (pin "1") (pinfunction "1_1") (pintype "passive"))
      (node (ref "R7") (pin "1") (pinfunction "1_1") (pintype "passive"))
      (node (ref "U$2") (pin "P$8") (pinfunction "8_P$8") (pintype "bidirectional"))
      (node (ref "U1") (pin "23") (pinfunction "PTA1_23") (pintype "bidirectional"))
    )
    (net (code "47") (name "SCL") (class "Default")
      (node (ref "R2") (pin "1") (pinfunction "1_1") (pintype "passive"))
      (node (ref "U1") (pin "44") (pinfunction "PTC1_44") (pintype "bidirectional"))
      (node (ref "U2") (pin "5") (pinfunction "SCL_5") (pintype "input"))
      (node (ref "U4") (pin "4") (pinfunction "SCL_4") (pintype "input"))
      (node (ref "U7") (pin "1") (pinfunction "SCL_1") (pintype "input"))
    )
    (net (code "48") (name "SDA") (class "Default")
      (node (ref "R3") (pin "1") (pinfunction "1_1") (pintype "passive"))
      (node (ref "U1") (pin "45") (pinfunction "PTC2_45") (pintype "bidirectional"))
      (node (ref "U2") (pin "6") (pinfunction "SDA_6") (pintype "bidirectional"))
      (node (ref "U4") (pin "3") (pinfunction "SDA_3") (pintype "bidirectional"))
      (node (ref "U7") (pin "2") (pinfunction "SDA_2") (pintype "bidirectional"))
    )
    (net (code "49") (name "SPI0_MISO") (class "Default")
      (node (ref "U6") (pin "2") (pinfunction "SO_2") (pintype "output"))
    )
    (net (code "50") (name "SPI0_MOSI") (class "Default")
      (node (ref "U1") (pin "59") (pinfunction "PTD2_59") (pintype "bidirectional"))
      (node (ref "U6") (pin "5") (pinfunction "SI/IO0_5") (pintype "bidirectional"))
    )
    (net (code "51") (name "SPI0_PCS0") (class "Default")
      (node (ref "U1") (pin "57") (pinfunction "PTD0_57") (pintype "bidirectional"))
      (node (ref "U6") (pin "1") (pinfunction "*CS_1") (pintype "input"))
    )
    (net (code "52") (name "SPI0_SCK") (class "Default")
      (node (ref "U1") (pin "58") (pinfunction "PTD1_58") (pintype "bidirectional"))
      (node (ref "U6") (pin "6") (pinfunction "SCK_6") (pintype "input"))
    )
    (net (code "53") (name "TCK") (class "Default")
      (node (ref "R5") (pin "2") (pinfunction "2_2") (pintype "passive"))
      (node (ref "U$2") (pin "P$4") (pinfunction "4_P$4") (pintype "bidirectional"))
      (node (ref "U1") (pin "22") (pinfunction "SWCLK_22") (pintype "bidirectional"))
    )
    (net (code "54") (name "TMS") (class "Default")
      (node (ref "R6") (pin "2") (pinfunction "2_2") (pintype "passive"))
      (node (ref "U$2") (pin "P$2") (pinfunction "2_P$2") (pintype "bidirectional"))
      (node (ref "U1") (pin "25") (pinfunction "SWDIO_25") (pintype "bidirectional"))
    )
    (net (code "55") (name "TX_0") (class "Default")
      (node (ref "L2") (pin "1") (pinfunction "1_1") (pintype "passive"))
      (node (ref "R8") (pin "2") (pinfunction "2_2") (pintype "passive"))
      (node (ref "U$2") (pin "P$6") (pinfunction "6_P$6") (pintype "bidirectional"))
      (node (ref "U1") (pin "24") (pinfunction "PTA2_24") (pintype "bidirectional"))
    )
    (net (code "56") (name "TX_LED") (class "Default")
      (node (ref "D1") (pin "A2") (pinfunction "G-_A2") (pintype "power_in"))
      (node (ref "U1") (pin "55") (pinfunction "PTC10_55") (pintype "bidirectional"))
    )
    (net (code "57") (name "unconnected-(J1-Pad4)") (class "Default")
      (node (ref "J1") (pin "4") (pinfunction "4_4") (pintype "bidirectional"))
    )
    (net (code "58") (name "unconnected-(S1-O1-PadP$1)") (class "Default")
      (node (ref "S1") (pin "P$1") (pinfunction "O1_P$1") (pintype "passive"))
    )
    (net (code "59") (name "unconnected-(U$3-Pad15_RESERVED)") (class "Default")
      (node (ref "U$3") (pin "15_RESERVED") (pinfunction "15_RESERVED_15_RESERVED") (pintype "bidirectional"))
    )
    (net (code "60") (name "unconnected-(U$3-Pad16_SDA2)") (class "Default")
      (node (ref "U$3") (pin "16_SDA2") (pinfunction "16_SDA2_16_SDA2") (pintype "bidirectional"))
    )
    (net (code "61") (name "unconnected-(U$3-Pad17_SCL2)") (class "Default")
      (node (ref "U$3") (pin "17_SCL2") (pinfunction "17_SCL2_17_SCL2") (pintype "bidirectional"))
    )
    (net (code "62") (name "unconnected-(U$3-Pad18_RESERVED)") (class "Default")
      (node (ref "U$3") (pin "18_RESERVED") (pinfunction "18_RESERVED_18_RESERVED") (pintype "bidirectional"))
    )
    (net (code "63") (name "unconnected-(U1-PTA4-Pad26)") (class "Default")
      (node (ref "U1") (pin "26") (pinfunction "PTA4_26") (pintype "bidirectional"))
    )
    (net (code "64") (name "unconnected-(U1-PTA5-Pad27)") (class "Default")
      (node (ref "U1") (pin "27") (pinfunction "PTA5_27") (pintype "bidirectional"))
    )
    (net (code "65") (name "unconnected-(U1-PTA12-Pad28)") (class "Default")
      (node (ref "U1") (pin "28") (pinfunction "PTA12_28") (pintype "bidirectional"))
    )
    (net (code "66") (name "unconnected-(U1-PTA13-Pad29)") (class "Default")
      (node (ref "U1") (pin "29") (pinfunction "PTA13_29") (pintype "bidirectional"))
    )
    (net (code "67") (name "unconnected-(U1-PTB2-Pad37)") (class "Default")
      (node (ref "U1") (pin "37") (pinfunction "PTB2_37") (pintype "bidirectional"))
    )
    (net (code "68") (name "unconnected-(U1-PTB3-Pad38)") (class "Default")
      (node (ref "U1") (pin "38") (pinfunction "PTB3_38") (pintype "bidirectional"))
    )
    (net (code "69") (name "unconnected-(U1-PTB16-Pad39)") (class "Default")
      (node (ref "U1") (pin "39") (pinfunction "PTB16_39") (pintype "bidirectional"))
    )
    (net (code "70") (name "unconnected-(U1-PTB17-Pad40)") (class "Default")
      (node (ref "U1") (pin "40") (pinfunction "PTB17_40") (pintype "bidirectional"))
    )
    (net (code "71") (name "unconnected-(U1-PTB18-Pad41)") (class "Default")
      (node (ref "U1") (pin "41") (pinfunction "PTB18_41") (pintype "bidirectional"))
    )
    (net (code "72") (name "unconnected-(U1-PTB19-Pad42)") (class "Default")
      (node (ref "U1") (pin "42") (pinfunction "PTB19_42") (pintype "bidirectional"))
    )
    (net (code "73") (name "unconnected-(U1-PTC0-Pad43)") (class "Default")
      (node (ref "U1") (pin "43") (pinfunction "PTC0_43") (pintype "bidirectional"))
    )
    (net (code "74") (name "unconnected-(U1-PTC3-Pad46)") (class "Default")
      (node (ref "U1") (pin "46") (pinfunction "PTC3_46") (pintype "bidirectional"))
    )
    (net (code "75") (name "unconnected-(U1-PTC4-Pad49)") (class "Default")
      (node (ref "U1") (pin "49") (pinfunction "PTC4_49") (pintype "bidirectional"))
    )
    (net (code "76") (name "unconnected-(U1-PTC5-Pad50)") (class "Default")
      (node (ref "U1") (pin "50") (pinfunction "PTC5_50") (pintype "bidirectional"))
    )
    (net (code "77") (name "unconnected-(U1-PTC6-Pad51)") (class "Default")
      (node (ref "U1") (pin "51") (pinfunction "PTC6_51") (pintype "bidirectional"))
    )
    (net (code "78") (name "unconnected-(U1-PTC7-Pad52)") (class "Default")
      (node (ref "U1") (pin "52") (pinfunction "PTC7_52") (pintype "bidirectional"))
    )
    (net (code "79") (name "unconnected-(U1-PTC8-Pad53)") (class "Default")
      (node (ref "U1") (pin "53") (pinfunction "PTC8_53") (pintype "bidirectional"))
    )
    (net (code "80") (name "unconnected-(U1-PTC9-Pad54)") (class "Default")
      (node (ref "U1") (pin "54") (pinfunction "PTC9_54") (pintype "bidirectional"))
    )
    (net (code "81") (name "unconnected-(U1-PTD3-Pad60)") (class "Default")
      (node (ref "U1") (pin "60") (pinfunction "PTD3_60") (pintype "bidirectional"))
    )
    (net (code "82") (name "unconnected-(U1-PTD5-Pad62)") (class "Default")
      (node (ref "U1") (pin "62") (pinfunction "PTD5_62") (pintype "bidirectional"))
    )
    (net (code "83") (name "unconnected-(U1-PTD6-Pad63)") (class "Default")
      (node (ref "U1") (pin "63") (pinfunction "PTD6_63") (pintype "bidirectional"))
    )
    (net (code "84") (name "unconnected-(U1-PTD7-Pad64)") (class "Default")
      (node (ref "U1") (pin "64") (pinfunction "PTD7_64") (pintype "bidirectional"))
    )
    (net (code "85") (name "unconnected-(U1-PTE0-Pad1)") (class "Default")
      (node (ref "U1") (pin "1") (pinfunction "PTE0_1") (pintype "bidirectional"))
    )
    (net (code "86") (name "unconnected-(U1-PTE1-Pad2)") (class "Default")
      (node (ref "U1") (pin "2") (pinfunction "PTE1_2") (pintype "bidirectional"))
    )
    (net (code "87") (name "unconnected-(U1-PTE20-Pad9)") (class "Default")
      (node (ref "U1") (pin "9") (pinfunction "PTE20_9") (pintype "bidirectional"))
    )
    (net (code "88") (name "unconnected-(U1-PTE21-Pad10)") (class "Default")
      (node (ref "U1") (pin "10") (pinfunction "PTE21_10") (pintype "bidirectional"))
    )
    (net (code "89") (name "unconnected-(U1-PTE23-Pad12)") (class "Default")
      (node (ref "U1") (pin "12") (pinfunction "PTE23_12") (pintype "bidirectional"))
    )
    (net (code "90") (name "unconnected-(U1-PTE24-Pad20)") (class "Default")
      (node (ref "U1") (pin "20") (pinfunction "PTE24_20") (pintype "bidirectional"))
    )
    (net (code "91") (name "unconnected-(U1-PTE25-Pad21)") (class "Default")
      (node (ref "U1") (pin "21") (pinfunction "PTE25_21") (pintype "bidirectional"))
    )
    (net (code "92") (name "unconnected-(U1-PTE29-Pad17)") (class "Default")
      (node (ref "U1") (pin "17") (pinfunction "PTE29_17") (pintype "bidirectional"))
    )
    (net (code "93") (name "unconnected-(U1-PTE31-Pad19)") (class "Default")
      (node (ref "U1") (pin "19") (pinfunction "PTE31_19") (pintype "bidirectional"))
    )
    (net (code "94") (name "unconnected-(U1-VOUT33-Pad7)") (class "Default")
      (node (ref "U1") (pin "7") (pinfunction "VOUT33_7") (pintype "bidirectional"))
    )
    (net (code "95") (name "unconnected-(U1-VREGIN-Pad8)") (class "Default")
      (node (ref "U1") (pin "8") (pinfunction "VREGIN_8") (pintype "bidirectional"))
    )
    (net (code "96") (name "unconnected-(U6-*HOLD-Pad7)") (class "Default")
      (node (ref "U6") (pin "7") (pinfunction "*HOLD_7") (pintype "input"))
    )
    (net (code "97") (name "unconnected-(U6-*WP-Pad3)") (class "Default")
      (node (ref "U6") (pin "3") (pinfunction "*WP_3") (pintype "input"))
    )
    (net (code "98") (name "unconnected-(U7-*WP-Pad12)") (class "Default")
      (node (ref "U7") (pin "12") (pinfunction "*WP_12") (pintype "input"))
    )
    (net (code "99") (name "unconnected-(U7-HVC{slash}A0-Pad16)") (class "Default")
      (node (ref "U7") (pin "16") (pinfunction "HVC/A0_16") (pintype "input"))
    )
    (net (code "100") (name "unconnected-(X2-Pad2)") (class "Default")
      (node (ref "X2") (pin "2") (pinfunction "2_2") (pintype "input"))
    )
  )
)
